# MEMS_BMI.net
KiCad netlist of a schematic drawn in EAGLE
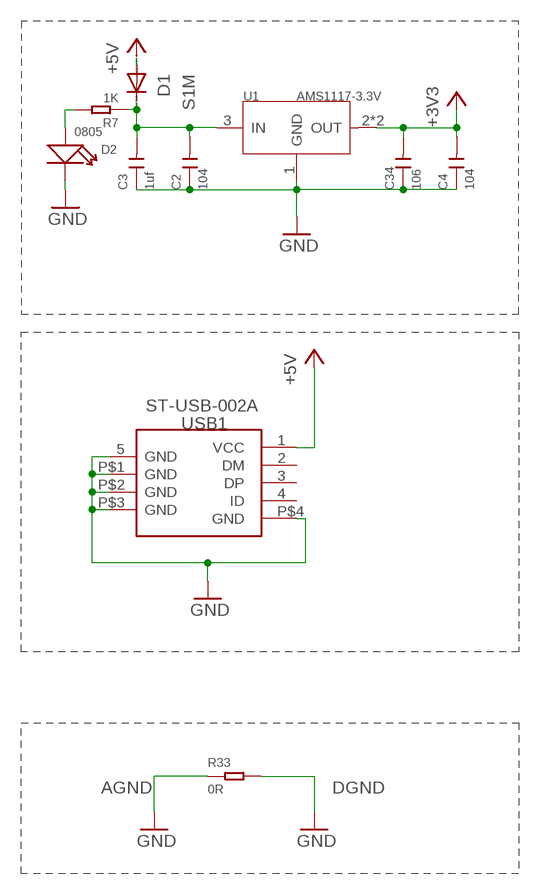
[diagram p0: schematic, sheet 1]
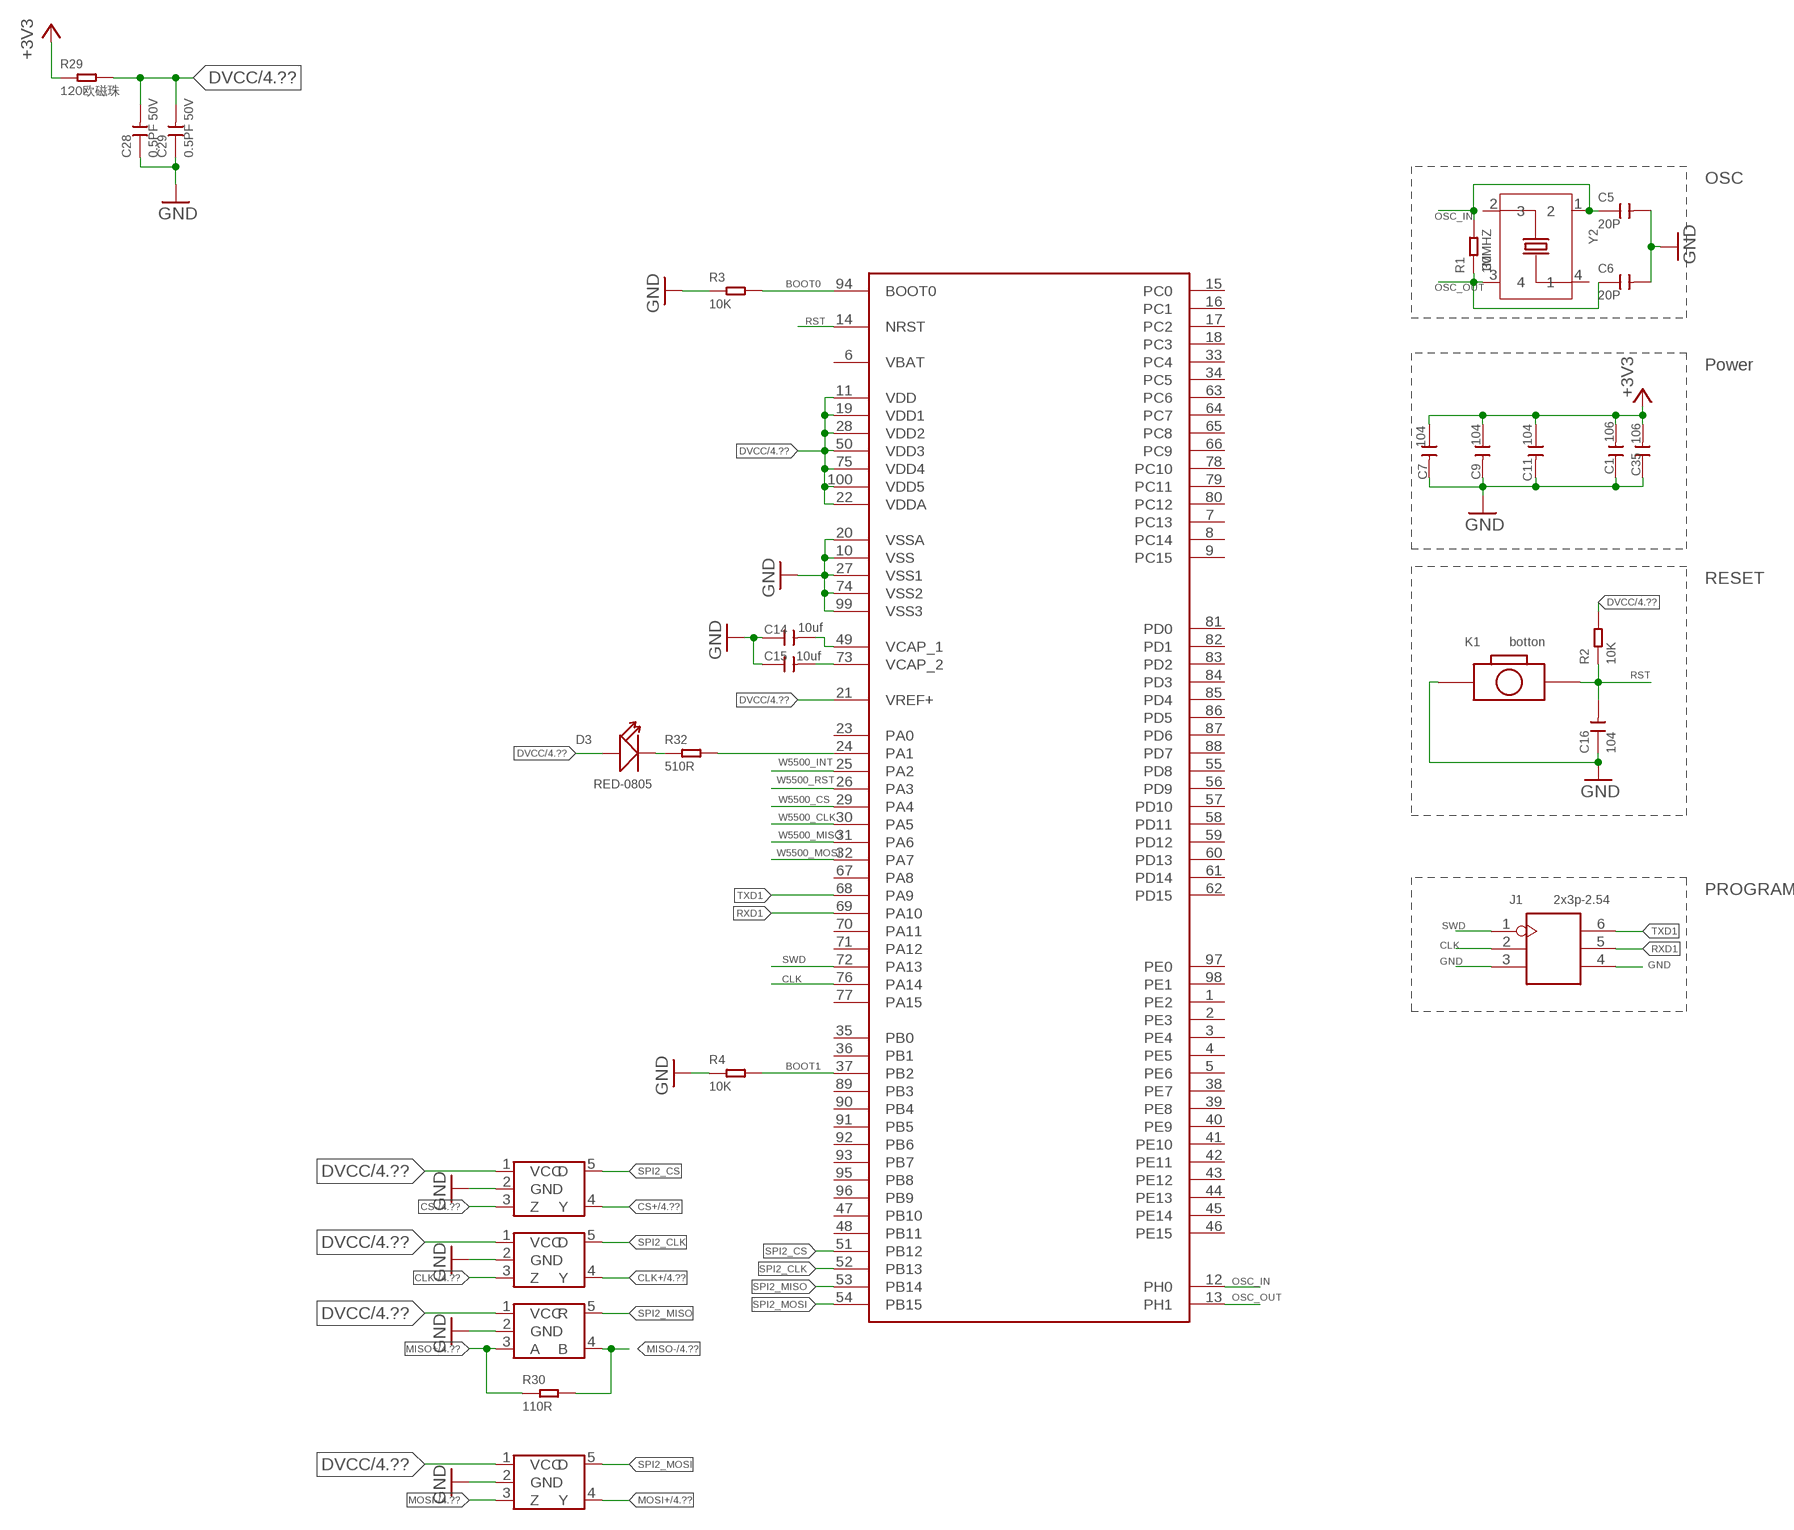
[diagram p1: schematic, sheet 2]
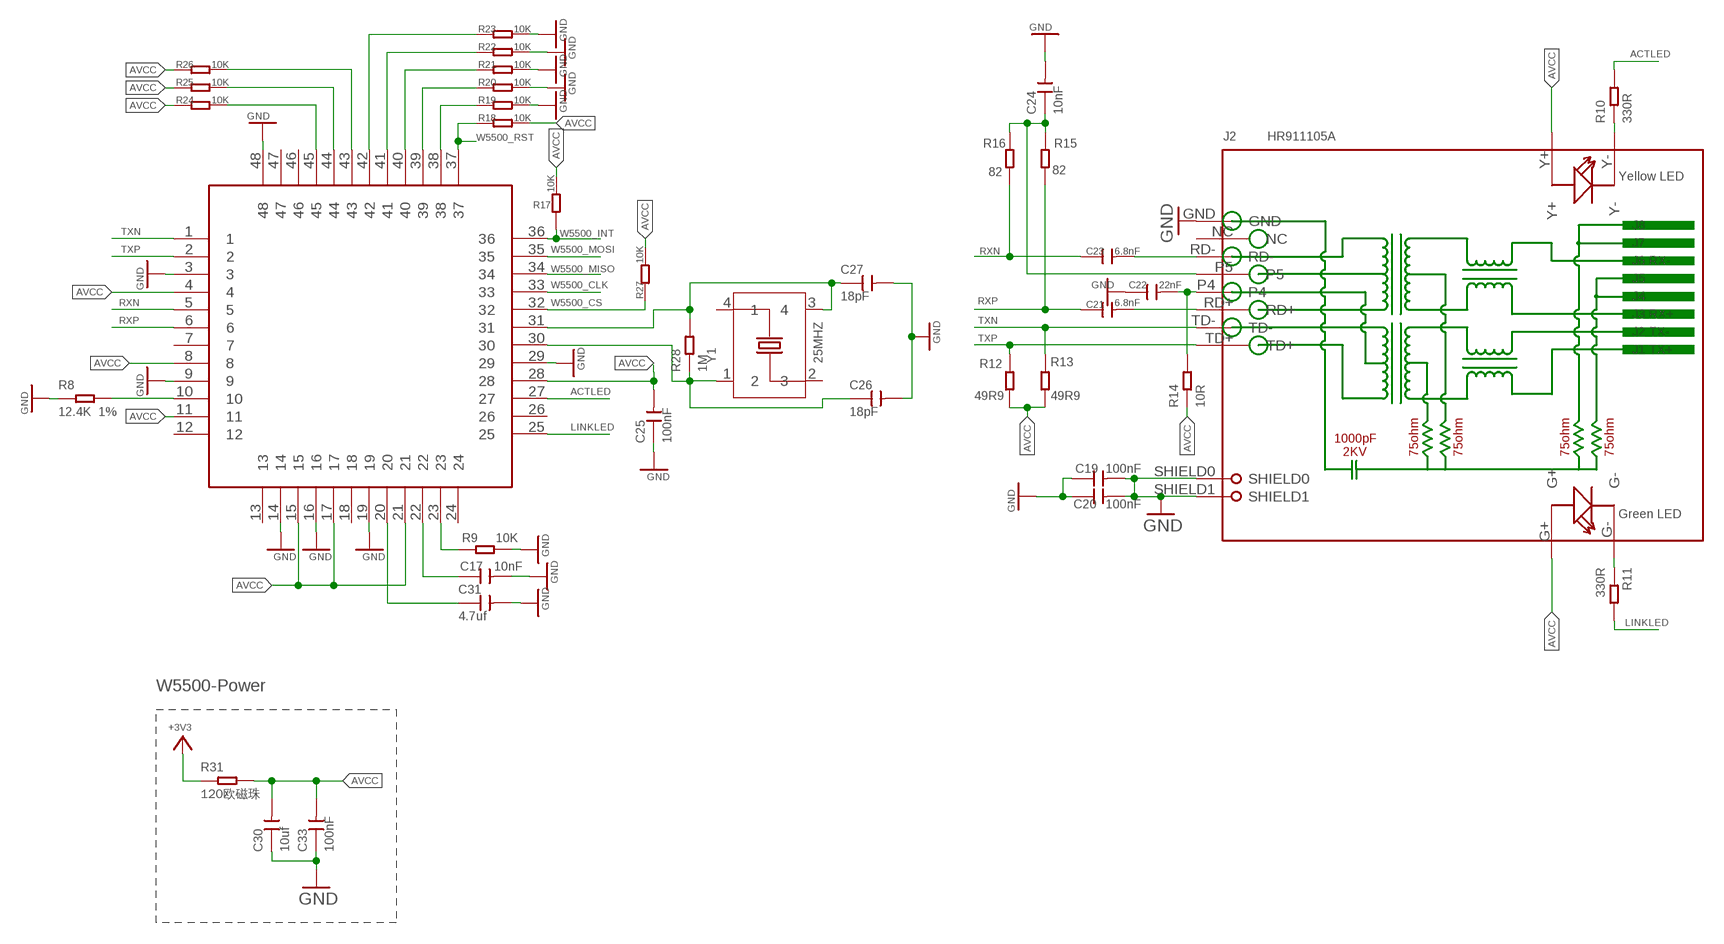
[diagram p2: schematic, sheet 3]
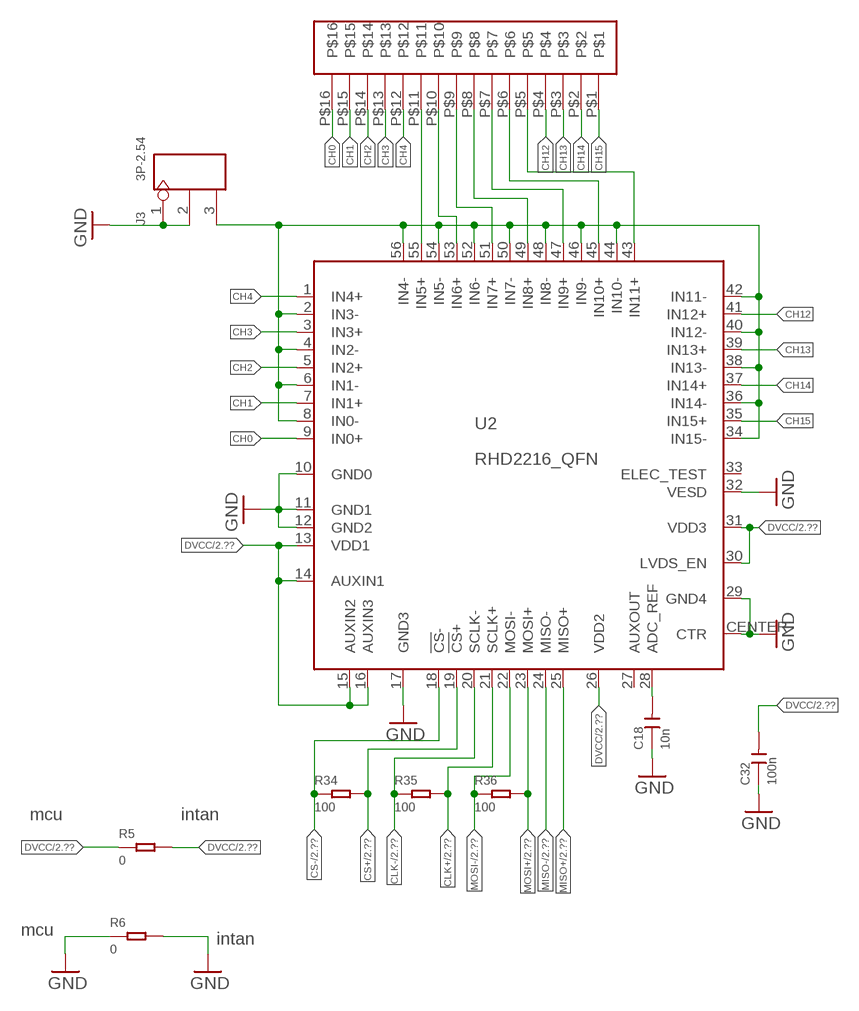
[diagram p3: schematic, sheet 4]

(export (version "E")
  (design (tool "Eeschema 10.0.6"))
  (components
    (comp (ref "C17")
      (value "10nF")
      (footprint "eagle-import:C0603")
      (libsource (lib "eagle-import") (part "CAP-(0603)"))
    )
    (comp (ref "C19")
      (value "100nF")
      (footprint "eagle-import:C0603")
      (libsource (lib "eagle-import") (part "CAP-(0603)"))
    )
    (comp (ref "C20")
      (value "100nF")
      (footprint "eagle-import:C0603")
      (libsource (lib "eagle-import") (part "CAP-(0603)"))
    )
    (comp (ref "C21")
      (value "6.8nF")
      (footprint "eagle-import:C0603")
      (libsource (lib "eagle-import") (part "CAP-(0603)"))
    )
    (comp (ref "C22")
      (value "22nF")
      (footprint "eagle-import:C0603")
      (libsource (lib "eagle-import") (part "CAP-(0603)"))
    )
    (comp (ref "C23")
      (value "6.8nF")
      (footprint "eagle-import:C0603")
      (libsource (lib "eagle-import") (part "CAP-(0603)"))
    )
    (comp (ref "C24")
      (value "10nF")
      (footprint "eagle-import:C0603")
      (libsource (lib "eagle-import") (part "CAP-(0603)"))
    )
    (comp (ref "C25")
      (value "100nF")
      (footprint "eagle-import:C0603")
      (libsource (lib "eagle-import") (part "CAP-(0603)"))
    )
    (comp (ref "C26")
      (value "18pF")
      (footprint "eagle-import:C0603")
      (libsource (lib "eagle-import") (part "CAP-(0603)"))
    )
    (comp (ref "C27")
      (value "18pF")
      (footprint "eagle-import:C0603")
      (libsource (lib "eagle-import") (part "CAP-(0603)"))
    )
    (comp (ref "C30")
      (value "10uf")
      (footprint "eagle-import:C0805")
      (fields (field (name "MPN") "CC0805KKX7R8BB105"))
      (libsource (lib "eagle-import") (part "CERAMIC-1UF-25V-10%-X7R(0805)"))
    )
    (comp (ref "C31")
      (value "4.7uf")
      (footprint "eagle-import:C0805")
      (fields (field (name "MPN") "CC0805KKX7R8BB105"))
      (libsource (lib "eagle-import") (part "CERAMIC-1UF-25V-10%-X7R(0805)"))
    )
    (comp (ref "C33")
      (value "100nF")
      (footprint "eagle-import:C0603")
      (libsource (lib "eagle-import") (part "CAP-(0603)"))
    )
    (comp (ref "J2")
      (value "HR911105A")
      (footprint "eagle-import:RJ45-12+2P-21.3X16.04X13.4MM")
      (libsource (lib "eagle-import") (part "DIP-RJ45-CONNECTOR(HR911105A)"))
    )
    (comp (ref "R8")
      (value "12.4K 1%")
      (footprint "eagle-import:R0603")
      (fields (field (name "MPN") "RC0603FR-071M1L"))
      (libsource (lib "eagle-import") (part "RES-(0603)"))
    )
    (comp (ref "R9")
      (value "10K")
      (footprint "eagle-import:R0603")
      (fields (field (name "MPN") "RC0603FR-071M1L"))
      (libsource (lib "eagle-import") (part "RES-(0603)"))
    )
    (comp (ref "R10")
      (value "330R")
      (footprint "eagle-import:R0603")
      (fields (field (name "MPN") "RC0603FR-071M1L"))
      (libsource (lib "eagle-import") (part "RES-(0603)"))
    )
    (comp (ref "R11")
      (value "330R")
      (footprint "eagle-import:R0603")
      (fields (field (name "MPN") "RC0603FR-071M1L"))
      (libsource (lib "eagle-import") (part "RES-(0603)"))
    )
    (comp (ref "R12")
      (value "49R9")
      (footprint "eagle-import:R0603")
      (fields (field (name "MPN") "RC0603FR-071M1L"))
      (libsource (lib "eagle-import") (part "RES-(0603)"))
    )
    (comp (ref "R13")
      (value "49R9")
      (footprint "eagle-import:R0603")
      (fields (field (name "MPN") "RC0603FR-071M1L"))
      (libsource (lib "eagle-import") (part "RES-(0603)"))
    )
    (comp (ref "R14")
      (value "10R")
      (footprint "eagle-import:R0603")
      (fields (field (name "MPN") "RC0603FR-071M1L"))
      (libsource (lib "eagle-import") (part "RES-(0603)"))
    )
    (comp (ref "R15")
      (value "82")
      (footprint "eagle-import:R0603")
      (fields (field (name "MPN") "RC0603FR-071M1L"))
      (libsource (lib "eagle-import") (part "RES-(0603)"))
    )
    (comp (ref "R16")
      (value "82")
      (footprint "eagle-import:R0603")
      (fields (field (name "MPN") "RC0603FR-071M1L"))
      (libsource (lib "eagle-import") (part "RES-(0603)"))
    )
    (comp (ref "R17")
      (value "10K")
      (footprint "eagle-import:R0603")
      (fields (field (name "MPN") "RC0603FR-071M1L"))
      (libsource (lib "eagle-import") (part "RES-(0603)"))
    )
    (comp (ref "R18")
      (value "10K")
      (footprint "eagle-import:R0603")
      (fields (field (name "MPN") "RC0603FR-071M1L"))
      (libsource (lib "eagle-import") (part "RES-(0603)"))
    )
    (comp (ref "R19")
      (value "10K")
      (footprint "eagle-import:R0603")
      (fields (field (name "MPN") "RC0603FR-071M1L"))
      (libsource (lib "eagle-import") (part "RES-(0603)"))
    )
    (comp (ref "R20")
      (value "10K")
      (footprint "eagle-import:R0603")
      (fields (field (name "MPN") "RC0603FR-071M1L"))
      (libsource (lib "eagle-import") (part "RES-(0603)"))
    )
    (comp (ref "R21")
      (value "10K")
      (footprint "eagle-import:R0603")
      (fields (field (name "MPN") "RC0603FR-071M1L"))
      (libsource (lib "eagle-import") (part "RES-(0603)"))
    )
    (comp (ref "R22")
      (value "10K")
      (footprint "eagle-import:R0603")
      (fields (field (name "MPN") "RC0603FR-071M1L"))
      (libsource (lib "eagle-import") (part "RES-(0603)"))
    )
    (comp (ref "R23")
      (value "10K")
      (footprint "eagle-import:R0603")
      (fields (field (name "MPN") "RC0603FR-071M1L"))
      (libsource (lib "eagle-import") (part "RES-(0603)"))
    )
    (comp (ref "R24")
      (value "10K")
      (footprint "eagle-import:R0603")
      (fields (field (name "MPN") "RC0603FR-071M1L"))
      (libsource (lib "eagle-import") (part "RES-(0603)"))
    )
    (comp (ref "R25")
      (value "10K")
      (footprint "eagle-import:R0603")
      (fields (field (name "MPN") "RC0603FR-071M1L"))
      (libsource (lib "eagle-import") (part "RES-(0603)"))
    )
    (comp (ref "R26")
      (value "10K")
      (footprint "eagle-import:R0603")
      (fields (field (name "MPN") "RC0603FR-071M1L"))
      (libsource (lib "eagle-import") (part "RES-(0603)"))
    )
    (comp (ref "R27")
      (value "10K")
      (footprint "eagle-import:R0603")
      (fields (field (name "MPN") "RC0603FR-071M1L"))
      (libsource (lib "eagle-import") (part "RES-(0603)"))
    )
    (comp (ref "R28")
      (value "1M")
      (footprint "eagle-import:R0603")
      (fields (field (name "MPN") "RC0603FR-071M1L"))
      (libsource (lib "eagle-import") (part "RES-(0603)"))
    )
    (comp (ref "R31")
      (value "120欧磁珠")
      (footprint "eagle-import:R0603")
      (fields (field (name "MPN") "RC0603FR-071M1L"))
      (libsource (lib "eagle-import") (part "RES-(0603)"))
    )
    (comp (ref "W5500-1")
      (value "W5500")
      (footprint "eagle-import:LQFP48")
      (libsource (lib "eagle-import") (part "W5500"))
    )
    (comp (ref "Y1")
      (value "25MHZ")
      (footprint "eagle-import:X4-SMD-3.2X2.5X0.7MM")
      (fields (field (name "MPN") "7M30000024"))
      (libsource (lib "eagle-import") (part "SMD-CRYSTAL-30MHZ-10PF-10PPM-60R(4P-3.2X2.5MM)"))
    )
    (comp (ref "C2")
      (value "104")
      (footprint "eagle-import:C0603")
      (libsource (lib "eagle-import") (part "CAP-(0603)"))
    )
    (comp (ref "C3")
      (value "1uf")
      (footprint "eagle-import:C0805")
      (fields (field (name "MPN") "CC0805KKX7R8BB105"))
      (libsource (lib "eagle-import") (part "CERAMIC-1UF-25V-10%-X7R(0805)"))
    )
    (comp (ref "C4")
      (value "104")
      (footprint "eagle-import:C0603")
      (libsource (lib "eagle-import") (part "CAP-(0603)"))
    )
    (comp (ref "C34")
      (value "106")
      (footprint "eagle-import:C0805")
      (fields (field (name "MPN") "CC0805KKX7R8BB105"))
      (libsource (lib "eagle-import") (part "CERAMIC-1UF-25V-10%-X7R(0805)"))
    )
    (comp (ref "D1")
      (value "S1M")
      (footprint "eagle-import:SMA")
      (libsource (lib "eagle-import") (part "S1M"))
    )
    (comp (ref "D2")
      (value "0805")
      (footprint "eagle-import:LED-0805")
      (fields (field (name "MPN") "17-215SURC/S530-A2/TR8"))
      (libsource (lib "eagle-import") (part "SMD-LED-CLEAR-RED(0805)"))
    )
    (comp (ref "R7")
      (value "1K")
      (footprint "eagle-import:R0603")
      (fields (field (name "MPN") "RC0603FR-071M1L"))
      (libsource (lib "eagle-import") (part "RES-(0603)"))
    )
    (comp (ref "R33")
      (value "0R")
      (footprint "eagle-import:R0603")
      (fields (field (name "MPN") "RC0603FR-071M1L"))
      (libsource (lib "eagle-import") (part "RES-(0603)"))
    )
    (comp (ref "U1")
      (value "AMS1117-3.3V")
      (footprint "eagle-import:SOT-223")
      (fields (field (name "MPN") "CJT1117-3.3"))
      (libsource (lib "eagle-import") (part "PMIC-CJT1117-3.3(SOT223)"))
    )
    (comp (ref "USB1")
      (value "ST-USB-002A")
      (footprint "eagle-import:MINIUSB5+4P-SMD-0.8-90D")
      (libsource (lib "eagle-import") (part "MINI-USB-RCPT-B-5PS-R/A-SMD(ST-USB-002A)"))
    )
    (comp (ref "C18")
      (value "10n")
      (footprint "eagle-import:C0603")
      (libsource (lib "eagle-import") (part "CAP-(0603)"))
    )
    (comp (ref "C32")
      (value "100n")
      (footprint "eagle-import:C0603")
      (libsource (lib "eagle-import") (part "CAP-(0603)"))
    )
    (comp (ref "J3")
      (value "3P-2.54")
      (footprint "eagle-import:H3-2.54")
      (fields (field (name "MPN") "P125-1103A0BS116A1"))
      (libsource (lib "eagle-import") (part "DIP-WHITE-MALE-HEADER-VERT(3P-2.54)"))
    )
    (comp (ref "R5")
      (value "0")
      (footprint "eagle-import:R0603")
      (fields (field (name "MPN") "RC0603FR-071M1L"))
      (libsource (lib "eagle-import") (part "RES-(0603)"))
    )
    (comp (ref "R6")
      (value "0")
      (footprint "eagle-import:R0603")
      (fields (field (name "MPN") "RC0603FR-071M1L"))
      (libsource (lib "eagle-import") (part "RES-(0603)"))
    )
    (comp (ref "R34")
      (value "100")
      (footprint "eagle-import:R0603")
      (fields (field (name "MPN") "RC0603FR-071M1L"))
      (libsource (lib "eagle-import") (part "RES-(0603)"))
    )
    (comp (ref "R35")
      (value "100")
      (footprint "eagle-import:R0603")
      (fields (field (name "MPN") "RC0603FR-071M1L"))
      (libsource (lib "eagle-import") (part "RES-(0603)"))
    )
    (comp (ref "R36")
      (value "100")
      (footprint "eagle-import:R0603")
      (fields (field (name "MPN") "RC0603FR-071M1L"))
      (libsource (lib "eagle-import") (part "RES-(0603)"))
    )
    (comp (ref "U$3")
      (value "PROBE")
      (footprint "eagle-import:PROBE-16-PIN")
      (libsource (lib "eagle-import") (part "PROBE"))
    )
    (comp (ref "U2")
      (value "RHD2216_QFN")
      (footprint "eagle-import:QFN56_8_X_8_LARGE")
      (libsource (lib "eagle-import") (part "RHD2216_QFN"))
    )
    (comp (ref "C1")
      (value "106")
      (footprint "eagle-import:C0805")
      (fields (field (name "MPN") "CC0805KKX7R8BB105"))
      (libsource (lib "eagle-import") (part "CERAMIC-1UF-25V-10%-X7R(0805)"))
    )
    (comp (ref "C5")
      (value "20P")
      (footprint "eagle-import:C0603")
      (libsource (lib "eagle-import") (part "CAP-(0603)"))
    )
    (comp (ref "C6")
      (value "20P")
      (footprint "eagle-import:C0603")
      (libsource (lib "eagle-import") (part "CAP-(0603)"))
    )
    (comp (ref "C7")
      (value "104")
      (footprint "eagle-import:C0603")
      (libsource (lib "eagle-import") (part "CAP-(0603)"))
    )
    (comp (ref "C9")
      (value "104")
      (footprint "eagle-import:C0603")
      (libsource (lib "eagle-import") (part "CAP-(0603)"))
    )
    (comp (ref "C11")
      (value "104")
      (footprint "eagle-import:C0603")
      (libsource (lib "eagle-import") (part "CAP-(0603)"))
    )
    (comp (ref "C14")
      (value "10uf")
      (footprint "eagle-import:C0805")
      (fields (field (name "MPN") "CC0805KKX7R8BB105"))
      (libsource (lib "eagle-import") (part "CERAMIC-1UF-25V-10%-X7R(0805)"))
    )
    (comp (ref "C15")
      (value "10uf")
      (footprint "eagle-import:C0805")
      (fields (field (name "MPN") "CC0805KKX7R8BB105"))
      (libsource (lib "eagle-import") (part "CERAMIC-1UF-25V-10%-X7R(0805)"))
    )
    (comp (ref "C16")
      (value "104")
      (footprint "eagle-import:C0603")
      (libsource (lib "eagle-import") (part "CAP-(0603)"))
    )
    (comp (ref "C28")
      (value "0.5PF 50V")
      (footprint "eagle-import:C0603")
      (libsource (lib "eagle-import") (part "CAP-(0603)"))
    )
    (comp (ref "C29")
      (value "0.5PF 50V")
      (footprint "eagle-import:C0603")
      (libsource (lib "eagle-import") (part "CAP-(0603)"))
    )
    (comp (ref "C35")
      (value "106")
      (footprint "eagle-import:C0805")
      (fields (field (name "MPN") "CC0805KKX7R8BB105"))
      (libsource (lib "eagle-import") (part "CERAMIC-1UF-25V-10%-X7R(0805)"))
    )
    (comp (ref "D3")
      (value "RED-0805")
      (footprint "eagle-import:LED-0805")
      (fields (field (name "MPN") "17-215SURC/S530-A2/TR8"))
      (libsource (lib "eagle-import") (part "SMD-LED-CLEAR-RED(0805)"))
    )
    (comp (ref "J1")
      (value "2x3p-2.54")
      (footprint "eagle-import:H2X3-2.54")
      (fields (field (name "MPN") "F185-1203A1BSYA1"))
      (libsource (lib "eagle-import") (part "DIP-BLACK-FEMALE-HEADER-VERT(2X3P-2.54)"))
    )
    (comp (ref "K1")
      (value "botton")
      (footprint "eagle-import:SW2-SMD-3.0X6.0_2.5")
      (fields (field (name "MPN") "B3U-1000P"))
      (libsource (lib "eagle-import") (part "SMD-BUTTON"))
    )
    (comp (ref "LVDS1-1")
      (value "SN65LVDS1")
      (footprint "eagle-import:DBV_R-PDSO-G5")
      (libsource (lib "eagle-import") (part "SN65LVDS1"))
    )
    (comp (ref "LVDS1-2")
      (value "SN65LVDS1")
      (footprint "eagle-import:DBV_R-PDSO-G5")
      (libsource (lib "eagle-import") (part "SN65LVDS1"))
    )
    (comp (ref "LVDS1-3")
      (value "SN65LVDS1")
      (footprint "eagle-import:DBV_R-PDSO-G5")
      (libsource (lib "eagle-import") (part "SN65LVDS1"))
    )
    (comp (ref "R1")
      (value "1M")
      (footprint "eagle-import:R0603")
      (fields (field (name "MPN") "RC0603FR-071M1L"))
      (libsource (lib "eagle-import") (part "RES-(0603)"))
    )
    (comp (ref "R2")
      (value "10K")
      (footprint "eagle-import:R0603")
      (fields (field (name "MPN") "RC0603FR-071M1L"))
      (libsource (lib "eagle-import") (part "RES-(0603)"))
    )
    (comp (ref "R3")
      (value "10K")
      (footprint "eagle-import:R0603")
      (fields (field (name "MPN") "RC0603FR-071M1L"))
      (libsource (lib "eagle-import") (part "RES-(0603)"))
    )
    (comp (ref "R4")
      (value "10K")
      (footprint "eagle-import:R0603")
      (fields (field (name "MPN") "RC0603FR-071M1L"))
      (libsource (lib "eagle-import") (part "RES-(0603)"))
    )
    (comp (ref "R29")
      (value "120欧磁珠")
      (footprint "eagle-import:R0603")
      (fields (field (name "MPN") "RC0603FR-071M1L"))
      (libsource (lib "eagle-import") (part "RES-(0603)"))
    )
    (comp (ref "R30")
      (value "110R")
      (footprint "eagle-import:R0603")
      (fields (field (name "MPN") "RC0603FR-071M1L"))
      (libsource (lib "eagle-import") (part "RES-(0603)"))
    )
    (comp (ref "R32")
      (value "510R")
      (footprint "eagle-import:R0603")
      (fields (field (name "MPN") "RC0603FR-071M1L"))
      (libsource (lib "eagle-import") (part "RES-(0603)"))
    )
    (comp (ref "U$1")
      (value "STM32F40XSTM32D40X")
      (footprint "eagle-import:LQFP100")
      (libsource (lib "eagle-import") (part "STM32F40XSTM32D40X"))
    )
    (comp (ref "U$2")
      (value "SN65LVDS2")
      (footprint "eagle-import:DBV_R-PDSO-G5")
      (libsource (lib "eagle-import") (part "SN65LVDS2"))
    )
    (comp (ref "Y2")
      (value "30MHZ")
      (footprint "eagle-import:X4-SMD-3.2X2.5X0.7MM")
      (fields (field (name "MPN") "7M30000024"))
      (libsource (lib "eagle-import") (part "SMD-CRYSTAL-30MHZ-10PF-10PPM-60R(4P-3.2X2.5MM)"))
    )
  )
  (nets
    (net (code "1") (name "+3V3") (class "Default")
      (node (ref "C1") (pin "2") (pinfunction "2_2") (pintype "passive"))
      (node (ref "C11") (pin "1") (pinfunction "1_1") (pintype "passive"))
      (node (ref "C34") (pin "2") (pinfunction "2_2") (pintype "passive"))
      (node (ref "C35") (pin "2") (pinfunction "2_2") (pintype "passive"))
      (node (ref "C4") (pin "2") (pinfunction "2_2") (pintype "passive"))
      (node (ref "C7") (pin "1") (pinfunction "1_1") (pintype "passive"))
      (node (ref "C9") (pin "1") (pinfunction "1_1") (pintype "passive"))
      (node (ref "R29") (pin "1") (pinfunction "1_1") (pintype "passive"))
      (node (ref "R31") (pin "1") (pinfunction "1_1") (pintype "passive"))
      (node (ref "U1") (pin "2") (pinfunction "OUT_2") (pintype "bidirectional"))
      (node (ref "U1") (pin "TER") (pinfunction "OUT_TER") (pintype "bidirectional"))
    )
    (net (code "2") (name "+5V") (class "Default")
      (node (ref "D1") (pin "A") (pinfunction "A_A") (pintype "passive"))
      (node (ref "USB1") (pin "1") (pinfunction "VCC_1") (pintype "bidirectional"))
    )
    (net (code "3") (name "ACTLED") (class "Default")
      (node (ref "R10") (pin "2") (pinfunction "2_2") (pintype "passive"))
      (node (ref "W5500-1") (pin "27") (pinfunction "27_27") (pintype "bidirectional"))
    )
    (net (code "4") (name "AVCC") (class "Default")
      (node (ref "C25") (pin "2") (pinfunction "2_2") (pintype "passive"))
      (node (ref "C30") (pin "2") (pinfunction "2_2") (pintype "passive"))
      (node (ref "C33") (pin "2") (pinfunction "2_2") (pintype "passive"))
      (node (ref "J2") (pin "G+") (pinfunction "G+_G+") (pintype "bidirectional"))
      (node (ref "J2") (pin "Y+") (pinfunction "Y+_Y+") (pintype "bidirectional"))
      (node (ref "R12") (pin "1") (pinfunction "1_1") (pintype "passive"))
      (node (ref "R13") (pin "1") (pinfunction "1_1") (pintype "passive"))
      (node (ref "R14") (pin "1") (pinfunction "1_1") (pintype "passive"))
      (node (ref "R17") (pin "2") (pinfunction "2_2") (pintype "passive"))
      (node (ref "R18") (pin "2") (pinfunction "2_2") (pintype "passive"))
      (node (ref "R24") (pin "1") (pinfunction "1_1") (pintype "passive"))
      (node (ref "R25") (pin "1") (pinfunction "1_1") (pintype "passive"))
      (node (ref "R26") (pin "1") (pinfunction "1_1") (pintype "passive"))
      (node (ref "R27") (pin "2") (pinfunction "2_2") (pintype "passive"))
      (node (ref "R31") (pin "2") (pinfunction "2_2") (pintype "passive"))
      (node (ref "W5500-1") (pin "11") (pinfunction "11_11") (pintype "bidirectional"))
      (node (ref "W5500-1") (pin "15") (pinfunction "15_15") (pintype "bidirectional"))
      (node (ref "W5500-1") (pin "17") (pinfunction "17_17") (pintype "bidirectional"))
      (node (ref "W5500-1") (pin "21") (pinfunction "21_21") (pintype "bidirectional"))
      (node (ref "W5500-1") (pin "28") (pinfunction "28_28") (pintype "bidirectional"))
      (node (ref "W5500-1") (pin "4") (pinfunction "4_4") (pintype "bidirectional"))
      (node (ref "W5500-1") (pin "8") (pinfunction "8_8") (pintype "bidirectional"))
    )
    (net (code "5") (name "BOOT0") (class "Default")
      (node (ref "R3") (pin "2") (pinfunction "2_2") (pintype "passive"))
      (node (ref "U$1") (pin "94") (pinfunction "BOOT0_94") (pintype "bidirectional"))
    )
    (net (code "6") (name "BOOT1") (class "Default")
      (node (ref "R4") (pin "2") (pinfunction "2_2") (pintype "passive"))
      (node (ref "U$1") (pin "37") (pinfunction "PB2_37") (pintype "bidirectional"))
    )
    (net (code "7") (name "CH0") (class "Default")
      (node (ref "U$3") (pin "P$16") (pinfunction "P$16_P$16") (pintype "bidirectional"))
      (node (ref "U2") (pin "9") (pinfunction "IN0+_9") (pintype "input"))
    )
    (net (code "8") (name "CH1") (class "Default")
      (node (ref "U$3") (pin "P$15") (pinfunction "P$15_P$15") (pintype "bidirectional"))
      (node (ref "U2") (pin "7") (pinfunction "IN1+_7") (pintype "input"))
    )
    (net (code "9") (name "CH2") (class "Default")
      (node (ref "U$3") (pin "P$14") (pinfunction "P$14_P$14") (pintype "bidirectional"))
      (node (ref "U2") (pin "5") (pinfunction "IN2+_5") (pintype "input"))
    )
    (net (code "10") (name "CH3") (class "Default")
      (node (ref "U$3") (pin "P$13") (pinfunction "P$13_P$13") (pintype "bidirectional"))
      (node (ref "U2") (pin "3") (pinfunction "IN3+_3") (pintype "input"))
    )
    (net (code "11") (name "CH4") (class "Default")
      (node (ref "U$3") (pin "P$12") (pinfunction "P$12_P$12") (pintype "bidirectional"))
      (node (ref "U2") (pin "1") (pinfunction "IN4+_1") (pintype "input"))
    )
    (net (code "12") (name "CH12") (class "Default")
      (node (ref "U$3") (pin "P$4") (pinfunction "P$4_P$4") (pintype "bidirectional"))
      (node (ref "U2") (pin "41") (pinfunction "IN12+_41") (pintype "input"))
    )
    (net (code "13") (name "CH13") (class "Default")
      (node (ref "U$3") (pin "P$3") (pinfunction "P$3_P$3") (pintype "bidirectional"))
      (node (ref "U2") (pin "39") (pinfunction "IN13+_39") (pintype "input"))
    )
    (net (code "14") (name "CH14") (class "Default")
      (node (ref "U$3") (pin "P$2") (pinfunction "P$2_P$2") (pintype "bidirectional"))
      (node (ref "U2") (pin "37") (pinfunction "IN14+_37") (pintype "input"))
    )
    (net (code "15") (name "CH15") (class "Default")
      (node (ref "U$3") (pin "P$1") (pinfunction "P$1_P$1") (pintype "bidirectional"))
      (node (ref "U2") (pin "35") (pinfunction "IN15+_35") (pintype "input"))
    )
    (net (code "16") (name "CLK") (class "Default")
      (node (ref "J1") (pin "2") (pinfunction "2_2") (pintype "bidirectional"))
      (node (ref "U$1") (pin "76") (pinfunction "PA14_76") (pintype "bidirectional"))
    )
    (net (code "17") (name "CLK+") (class "Default")
      (node (ref "LVDS1-2") (pin "4") (pinfunction "Y_4") (pintype "bidirectional"))
      (node (ref "R35") (pin "2") (pinfunction "2_2") (pintype "passive"))
      (node (ref "U2") (pin "21") (pinfunction "SCLK+_21") (pintype "input"))
    )
    (net (code "18") (name "CLK-") (class "Default")
      (node (ref "LVDS1-2") (pin "3") (pinfunction "Z_3") (pintype "bidirectional"))
      (node (ref "R35") (pin "1") (pinfunction "1_1") (pintype "passive"))
      (node (ref "U2") (pin "20") (pinfunction "SCLK-_20") (pintype "input"))
    )
    (net (code "19") (name "CS+") (class "Default")
      (node (ref "LVDS1-1") (pin "4") (pinfunction "Y_4") (pintype "bidirectional"))
      (node (ref "R34") (pin "2") (pinfunction "2_2") (pintype "passive"))
      (node (ref "U2") (pin "19") (pinfunction "~{CS}+_19") (pintype "input"))
    )
    (net (code "20") (name "CS-") (class "Default")
      (node (ref "LVDS1-1") (pin "3") (pinfunction "Z_3") (pintype "bidirectional"))
      (node (ref "R34") (pin "1") (pinfunction "1_1") (pintype "passive"))
      (node (ref "U2") (pin "18") (pinfunction "~{CS}-_18") (pintype "input"))
    )
    (net (code "21") (name "DVCC") (class "Default")
      (node (ref "C28") (pin "2") (pinfunction "2_2") (pintype "passive"))
      (node (ref "C29") (pin "2") (pinfunction "2_2") (pintype "passive"))
      (node (ref "C32") (pin "2") (pinfunction "2_2") (pintype "passive"))
      (node (ref "D3") (pin "+") (pinfunction "+_+") (pintype "passive"))
      (node (ref "LVDS1-1") (pin "1") (pinfunction "VCC_1") (pintype "bidirectional"))
      (node (ref "LVDS1-2") (pin "1") (pinfunction "VCC_1") (pintype "bidirectional"))
      (node (ref "LVDS1-3") (pin "1") (pinfunction "VCC_1") (pintype "bidirectional"))
      (node (ref "R2") (pin "2") (pinfunction "2_2") (pintype "passive"))
      (node (ref "R29") (pin "2") (pinfunction "2_2") (pintype "passive"))
      (node (ref "R5") (pin "1") (pinfunction "1_1") (pintype "passive"))
      (node (ref "R5") (pin "2") (pinfunction "2_2") (pintype "passive"))
      (node (ref "U$1") (pin "100") (pinfunction "VDD5_100") (pintype "bidirectional"))
      (node (ref "U$1") (pin "11") (pinfunction "VDD_11") (pintype "bidirectional"))
      (node (ref "U$1") (pin "19") (pinfunction "VDD1_19") (pintype "bidirectional"))
      (node (ref "U$1") (pin "21") (pinfunction "VREF+_21") (pintype "bidirectional"))
      (node (ref "U$1") (pin "22") (pinfunction "VDDA_22") (pintype "bidirectional"))
      (node (ref "U$1") (pin "28") (pinfunction "VDD2_28") (pintype "bidirectional"))
      (node (ref "U$1") (pin "50") (pinfunction "VDD3_50") (pintype "bidirectional"))
      (node (ref "U$1") (pin "75") (pinfunction "VDD4_75") (pintype "bidirectional"))
      (node (ref "U$2") (pin "1") (pinfunction "VCC_1") (pintype "bidirectional"))
      (node (ref "U2") (pin "13") (pinfunction "VDD1_13") (pintype "power_in"))
      (node (ref "U2") (pin "14") (pinfunction "AUXIN1_14") (pintype "input"))
      (node (ref "U2") (pin "15") (pinfunction "AUXIN2_15") (pintype "input"))
      (node (ref "U2") (pin "16") (pinfunction "AUXIN3_16") (pintype "input"))
      (node (ref "U2") (pin "26") (pinfunction "VDD2_26") (pintype "power_in"))
      (node (ref "U2") (pin "30") (pinfunction "LVDS_EN_30") (pintype "input"))
      (node (ref "U2") (pin "31") (pinfunction "VDD3_31") (pintype "power_in"))
    )
    (net (code "22") (name "GND") (class "Default")
      (node (ref "C1") (pin "1") (pinfunction "1_1") (pintype "passive"))
      (node (ref "C11") (pin "2") (pinfunction "2_2") (pintype "passive"))
      (node (ref "C14") (pin "1") (pinfunction "1_1") (pintype "passive"))
      (node (ref "C15") (pin "1") (pinfunction "1_1") (pintype "passive"))
      (node (ref "C16") (pin "1") (pinfunction "1_1") (pintype "passive"))
      (node (ref "C17") (pin "2") (pinfunction "2_2") (pintype "passive"))
      (node (ref "C18") (pin "1") (pinfunction "1_1") (pintype "passive"))
      (node (ref "C19") (pin "1") (pinfunction "1_1") (pintype "passive"))
      (node (ref "C19") (pin "2") (pinfunction "2_2") (pintype "passive"))
      (node (ref "C2") (pin "1") (pinfunction "1_1") (pintype "passive"))
      (node (ref "C20") (pin "1") (pinfunction "1_1") (pintype "passive"))
      (node (ref "C20") (pin "2") (pinfunction "2_2") (pintype "passive"))
      (node (ref "C22") (pin "1") (pinfunction "1_1") (pintype "passive"))
      (node (ref "C24") (pin "2") (pinfunction "2_2") (pintype "passive"))
      (node (ref "C25") (pin "1") (pinfunction "1_1") (pintype "passive"))
      (node (ref "C26") (pin "2") (pinfunction "2_2") (pintype "passive"))
      (node (ref "C27") (pin "2") (pinfunction "2_2") (pintype "passive"))
      (node (ref "C28") (pin "1") (pinfunction "1_1") (pintype "passive"))
      (node (ref "C29") (pin "1") (pinfunction "1_1") (pintype "passive"))
      (node (ref "C3") (pin "1") (pinfunction "1_1") (pintype "passive"))
      (node (ref "C30") (pin "1") (pinfunction "1_1") (pintype "passive"))
      (node (ref "C31") (pin "2") (pinfunction "2_2") (pintype "passive"))
      (node (ref "C32") (pin "1") (pinfunction "1_1") (pintype "passive"))
      (node (ref "C33") (pin "1") (pinfunction "1_1") (pintype "passive"))
      (node (ref "C34") (pin "1") (pinfunction "1_1") (pintype "passive"))
      (node (ref "C35") (pin "1") (pinfunction "1_1") (pintype "passive"))
      (node (ref "C4") (pin "1") (pinfunction "1_1") (pintype "passive"))
      (node (ref "C5") (pin "2") (pinfunction "2_2") (pintype "passive"))
      (node (ref "C6") (pin "2") (pinfunction "2_2") (pintype "passive"))
      (node (ref "C7") (pin "2") (pinfunction "2_2") (pintype "passive"))
      (node (ref "C9") (pin "2") (pinfunction "2_2") (pintype "passive"))
      (node (ref "D2") (pin "-") (pinfunction "-_-") (pintype "passive"))
      (node (ref "J1") (pin "3") (pinfunction "3_3") (pintype "bidirectional"))
      (node (ref "J1") (pin "4") (pinfunction "4_4") (pintype "bidirectional"))
      (node (ref "J2") (pin "GND") (pinfunction "GND_GND") (pintype "bidirectional"))
      (node (ref "J2") (pin "SHIELD0") (pinfunction "SHIELD0_SHIELD0") (pintype "bidirectional"))
      (node (ref "J2") (pin "SHIELD1") (pinfunction "SHIELD1_SHIELD1") (pintype "bidirectional"))
      (node (ref "J3") (pin "1") (pinfunction "P$1_1") (pintype "bidirectional"))
      (node (ref "J3") (pin "2") (pinfunction "P$2_2") (pintype "bidirectional"))
      (node (ref "K1") (pin "1") (pinfunction "1_1") (pintype "bidirectional"))
      (node (ref "LVDS1-1") (pin "2") (pinfunction "GND_2") (pintype "bidirectional"))
      (node (ref "LVDS1-2") (pin "2") (pinfunction "GND_2") (pintype "bidirectional"))
      (node (ref "LVDS1-3") (pin "2") (pinfunction "GND_2") (pintype "bidirectional"))
      (node (ref "R19") (pin "2") (pinfunction "2_2") (pintype "passive"))
      (node (ref "R20") (pin "2") (pinfunction "2_2") (pintype "passive"))
      (node (ref "R21") (pin "2") (pinfunction "2_2") (pintype "passive"))
      (node (ref "R22") (pin "2") (pinfunction "2_2") (pintype "passive"))
      (node (ref "R23") (pin "2") (pinfunction "2_2") (pintype "passive"))
      (node (ref "R3") (pin "1") (pinfunction "1_1") (pintype "passive"))
      (node (ref "R33") (pin "1") (pinfunction "1_1") (pintype "passive"))
      (node (ref "R33") (pin "2") (pinfunction "2_2") (pintype "passive"))
      (node (ref "R4") (pin "1") (pinfunction "1_1") (pintype "passive"))
      (node (ref "R6") (pin "1") (pinfunction "1_1") (pintype "passive"))
      (node (ref "R6") (pin "2") (pinfunction "2_2") (pintype "passive"))
      (node (ref "R8") (pin "1") (pinfunction "1_1") (pintype "passive"))
      (node (ref "R9") (pin "2") (pinfunction "2_2") (pintype "passive"))
      (node (ref "U$1") (pin "10") (pinfunction "VSS_10") (pintype "bidirectional"))
      (node (ref "U$1") (pin "20") (pinfunction "VSSA_20") (pintype "bidirectional"))
      (node (ref "U$1") (pin "27") (pinfunction "VSS1_27") (pintype "bidirectional"))
      (node (ref "U$1") (pin "74") (pinfunction "VSS2_74") (pintype "bidirectional"))
      (node (ref "U$1") (pin "99") (pinfunction "VSS3_99") (pintype "bidirectional"))
      (node (ref "U$2") (pin "2") (pinfunction "GND_2") (pintype "bidirectional"))
      (node (ref "U1") (pin "1") (pinfunction "GND_1") (pintype "bidirectional"))
      (node (ref "U2") (pin "10") (pinfunction "GND0_10") (pintype "input"))
      (node (ref "U2") (pin "11") (pinfunction "GND1_11") (pintype "power_in"))
      (node (ref "U2") (pin "12") (pinfunction "GND2_12") (pintype "power_in"))
      (node (ref "U2") (pin "17") (pinfunction "GND3_17") (pintype "power_in"))
      (node (ref "U2") (pin "29") (pinfunction "GND4_29") (pintype "power_in"))
      (node (ref "U2") (pin "32") (pinfunction "VESD_32") (pintype "power_in"))
      (node (ref "U2") (pin "CENTER") (pinfunction "CTR_CENTER") (pintype "power_in"))
      (node (ref "USB1") (pin "5") (pinfunction "GND_5") (pintype "bidirectional"))
      (node (ref "USB1") (pin "P$1") (pinfunction "GND_P$1") (pintype "bidirectional"))
      (node (ref "USB1") (pin "P$2") (pinfunction "GND_P$2") (pintype "bidirectional"))
      (node (ref "USB1") (pin "P$3") (pinfunction "GND_P$3") (pintype "bidirectional"))
      (node (ref "USB1") (pin "P$4") (pinfunction "GND_P$4") (pintype "bidirectional"))
      (node (ref "W5500-1") (pin "14") (pinfunction "14_14") (pintype "bidirectional"))
      (node (ref "W5500-1") (pin "16") (pinfunction "16_16") (pintype "bidirectional"))
      (node (ref "W5500-1") (pin "19") (pinfunction "19_19") (pintype "bidirectional"))
      (node (ref "W5500-1") (pin "29") (pinfunction "29_29") (pintype "bidirectional"))
      (node (ref "W5500-1") (pin "3") (pinfunction "3_3") (pintype "bidirectional"))
      (node (ref "W5500-1") (pin "48") (pinfunction "48_48") (pintype "bidirectional"))
      (node (ref "W5500-1") (pin "9") (pinfunction "9_9") (pintype "bidirectional"))
    )
    (net (code "23") (name "LINKLED") (class "Default")
      (node (ref "R11") (pin "2") (pinfunction "2_2") (pintype "passive"))
      (node (ref "W5500-1") (pin "25") (pinfunction "25_25") (pintype "bidirectional"))
    )
    (net (code "24") (name "MISO+") (class "Default")
      (node (ref "R30") (pin "1") (pinfunction "1_1") (pintype "passive"))
      (node (ref "U$2") (pin "3") (pinfunction "A_3") (pintype "bidirectional"))
      (node (ref "U2") (pin "25") (pinfunction "MISO+_25") (pintype "output"))
    )
    (net (code "25") (name "MISO-") (class "Default")
      (node (ref "R30") (pin "2") (pinfunction "2_2") (pintype "passive"))
      (node (ref "U$2") (pin "4") (pinfunction "B_4") (pintype "bidirectional"))
      (node (ref "U2") (pin "24") (pinfunction "MISO-_24") (pintype "output"))
    )
    (net (code "26") (name "MOSI+") (class "Default")
      (node (ref "LVDS1-3") (pin "4") (pinfunction "Y_4") (pintype "bidirectional"))
      (node (ref "R36") (pin "2") (pinfunction "2_2") (pintype "passive"))
      (node (ref "U2") (pin "23") (pinfunction "MOSI+_23") (pintype "input"))
    )
    (net (code "27") (name "MOSI-") (class "Default")
      (node (ref "LVDS1-3") (pin "3") (pinfunction "Z_3") (pintype "bidirectional"))
      (node (ref "R36") (pin "1") (pinfunction "1_1") (pintype "passive"))
      (node (ref "U2") (pin "22") (pinfunction "MOSI-_22") (pintype "input"))
    )
    (net (code "28") (name "Net-(C17-Pad1)") (class "Default")
      (node (ref "C17") (pin "1") (pinfunction "1_1") (pintype "passive"))
      (node (ref "W5500-1") (pin "22") (pinfunction "22_22") (pintype "bidirectional"))
    )
    (net (code "29") (name "Net-(C21-Pad2)") (class "Default")
      (node (ref "C21") (pin "2") (pinfunction "2_2") (pintype "passive"))
      (node (ref "J2") (pin "RD+") (pinfunction "RD+_RD+") (pintype "bidirectional"))
    )
    (net (code "30") (name "Net-(C22-Pad2)") (class "Default")
      (node (ref "C22") (pin "2") (pinfunction "2_2") (pintype "passive"))
      (node (ref "J2") (pin "P4") (pinfunction "P4_P4") (pintype "bidirectional"))
      (node (ref "R14") (pin "2") (pinfunction "2_2") (pintype "passive"))
    )
    (net (code "31") (name "Net-(C23-Pad2)") (class "Default")
      (node (ref "C23") (pin "2") (pinfunction "2_2") (pintype "passive"))
      (node (ref "J2") (pin "RD-") (pinfunction "RD-_RD-") (pintype "bidirectional"))
    )
    (net (code "32") (name "Net-(C24-Pad1)") (class "Default")
      (node (ref "C24") (pin "1") (pinfunction "1_1") (pintype "passive"))
      (node (ref "J2") (pin "P5") (pinfunction "P5_P5") (pintype "bidirectional"))
      (node (ref "R15") (pin "2") (pinfunction "2_2") (pintype "passive"))
      (node (ref "R16") (pin "2") (pinfunction "2_2") (pintype "passive"))
    )
    (net (code "33") (name "Net-(C31-Pad1)") (class "Default")
      (node (ref "C31") (pin "1") (pinfunction "1_1") (pintype "passive"))
      (node (ref "W5500-1") (pin "20") (pinfunction "20_20") (pintype "bidirectional"))
    )
    (net (code "34") (name "Net-(D2-Pad+)") (class "Default")
      (node (ref "D2") (pin "+") (pinfunction "+_+") (pintype "passive"))
      (node (ref "R7") (pin "2") (pinfunction "2_2") (pintype "passive"))
    )
    (net (code "35") (name "Net-(D3-Pad-)") (class "Default")
      (node (ref "D3") (pin "-") (pinfunction "-_-") (pintype "passive"))
      (node (ref "R32") (pin "1") (pinfunction "1_1") (pintype "passive"))
    )
    (net (code "36") (name "Net-(J2-PadG-)") (class "Default")
      (node (ref "J2") (pin "G-") (pinfunction "G-_G-") (pintype "bidirectional"))
      (node (ref "R11") (pin "1") (pinfunction "1_1") (pintype "passive"))
    )
    (net (code "37") (name "Net-(J2-PadY-)") (class "Default")
      (node (ref "J2") (pin "Y-") (pinfunction "Y-_Y-") (pintype "bidirectional"))
      (node (ref "R10") (pin "1") (pinfunction "1_1") (pintype "passive"))
    )
    (net (code "38") (name "Net-(J3-P$3)") (class "Default")
      (node (ref "J3") (pin "3") (pinfunction "P$3_3") (pintype "bidirectional"))
      (node (ref "U2") (pin "2") (pinfunction "IN3-_2") (pintype "input"))
      (node (ref "U2") (pin "34") (pinfunction "IN15-_34") (pintype "input"))
      (node (ref "U2") (pin "36") (pinfunction "IN14-_36") (pintype "input"))
      (node (ref "U2") (pin "38") (pinfunction "IN13-_38") (pintype "input"))
      (node (ref "U2") (pin "4") (pinfunction "IN2-_4") (pintype "input"))
      (node (ref "U2") (pin "40") (pinfunction "IN12-_40") (pintype "input"))
      (node (ref "U2") (pin "42") (pinfunction "IN11-_42") (pintype "input"))
      (node (ref "U2") (pin "44") (pinfunction "IN10-_44") (pintype "input"))
      (node (ref "U2") (pin "46") (pinfunction "IN9-_46") (pintype "input"))
      (node (ref "U2") (pin "48") (pinfunction "IN8-_48") (pintype "input"))
      (node (ref "U2") (pin "50") (pinfunction "IN7-_50") (pintype "input"))
      (node (ref "U2") (pin "52") (pinfunction "IN6-_52") (pintype "input"))
      (node (ref "U2") (pin "54") (pinfunction "IN5-_54") (pintype "input"))
      (node (ref "U2") (pin "56") (pinfunction "IN4-_56") (pintype "input"))
      (node (ref "U2") (pin "6") (pinfunction "IN1-_6") (pintype "input"))
      (node (ref "U2") (pin "8") (pinfunction "IN0-_8") (pintype "input"))
    )
    (net (code "39") (name "Net-(R8-Pad2)") (class "Default")
      (node (ref "R8") (pin "2") (pinfunction "2_2") (pintype "passive"))
      (node (ref "W5500-1") (pin "10") (pinfunction "10_10") (pintype "bidirectional"))
    )
    (net (code "40") (name "Net-(R9-Pad1)") (class "Default")
      (node (ref "R9") (pin "1") (pinfunction "1_1") (pintype "passive"))
      (node (ref "W5500-1") (pin "23") (pinfunction "23_23") (pintype "bidirectional"))
    )
    (net (code "41") (name "Net-(R19-Pad1)") (class "Default")
      (node (ref "R19") (pin "1") (pinfunction "1_1") (pintype "passive"))
      (node (ref "W5500-1") (pin "38") (pinfunction "38_38") (pintype "bidirectional"))
    )
    (net (code "42") (name "Net-(R20-Pad1)") (class "Default")
      (node (ref "R20") (pin "1") (pinfunction "1_1") (pintype "passive"))
      (node (ref "W5500-1") (pin "39") (pinfunction "39_39") (pintype "bidirectional"))
    )
    (net (code "43") (name "Net-(R21-Pad1)") (class "Default")
      (node (ref "R21") (pin "1") (pinfunction "1_1") (pintype "passive"))
      (node (ref "W5500-1") (pin "40") (pinfunction "40_40") (pintype "bidirectional"))
    )
    (net (code "44") (name "Net-(R22-Pad1)") (class "Default")
      (node (ref "R22") (pin "1") (pinfunction "1_1") (pintype "passive"))
      (node (ref "W5500-1") (pin "41") (pinfunction "41_41") (pintype "bidirectional"))
    )
    (net (code "45") (name "Net-(R23-Pad1)") (class "Default")
      (node (ref "R23") (pin "1") (pinfunction "1_1") (pintype "passive"))
      (node (ref "W5500-1") (pin "42") (pinfunction "42_42") (pintype "bidirectional"))
    )
    (net (code "46") (name "Net-(R24-Pad2)") (class "Default")
      (node (ref "R24") (pin "2") (pinfunction "2_2") (pintype "passive"))
      (node (ref "W5500-1") (pin "45") (pinfunction "45_45") (pintype "bidirectional"))
    )
    (net (code "47") (name "Net-(R25-Pad2)") (class "Default")
      (node (ref "R25") (pin "2") (pinfunction "2_2") (pintype "passive"))
      (node (ref "W5500-1") (pin "44") (pinfunction "44_44") (pintype "bidirectional"))
    )
    (net (code "48") (name "Net-(R26-Pad2)") (class "Default")
      (node (ref "R26") (pin "2") (pinfunction "2_2") (pintype "passive"))
      (node (ref "W5500-1") (pin "43") (pinfunction "43_43") (pintype "bidirectional"))
    )
    (net (code "49") (name "Net-(U$1-PA1)") (class "Default")
      (node (ref "R32") (pin "2") (pinfunction "2_2") (pintype "passive"))
      (node (ref "U$1") (pin "24") (pinfunction "PA1_24") (pintype "bidirectional"))
    )
    (net (code "50") (name "Net-(U$1-VCAP_1)") (class "Default")
      (node (ref "C14") (pin "2") (pinfunction "2_2") (pintype "passive"))
      (node (ref "U$1") (pin "49") (pinfunction "VCAP_1_49") (pintype "bidirectional"))
    )
    (net (code "51") (name "Net-(U$1-VCAP_2)") (class "Default")
      (node (ref "C15") (pin "2") (pinfunction "2_2") (pintype "passive"))
      (node (ref "U$1") (pin "73") (pinfunction "VCAP_2_73") (pintype "bidirectional"))
    )
    (net (code "52") (name "Net-(U1-IN)") (class "Default")
      (node (ref "C2") (pin "2") (pinfunction "2_2") (pintype "passive"))
      (node (ref "C3") (pin "2") (pinfunction "2_2") (pintype "passive"))
      (node (ref "D1") (pin "C") (pinfunction "C_C") (pintype "passive"))
      (node (ref "R7") (pin "1") (pinfunction "1_1") (pintype "passive"))
      (node (ref "U1") (pin "3") (pinfunction "IN_3") (pintype "bidirectional"))
    )
    (net (code "53") (name "Net-(U2-ADC_REF)") (class "Default")
      (node (ref "C18") (pin "2") (pinfunction "2_2") (pintype "passive"))
      (node (ref "U2") (pin "28") (pinfunction "ADC_REF_28") (pintype "passive"))
    )
    (net (code "54") (name "Net-(U2-IN5+)") (class "Default")
      (node (ref "U$3") (pin "P$11") (pinfunction "P$11_P$11") (pintype "bidirectional"))
      (node (ref "U2") (pin "55") (pinfunction "IN5+_55") (pintype "input"))
    )
    (net (code "55") (name "Net-(U2-IN6+)") (class "Default")
      (node (ref "U$3") (pin "P$10") (pinfunction "P$10_P$10") (pintype "bidirectional"))
      (node (ref "U2") (pin "53") (pinfunction "IN6+_53") (pintype "input"))
    )
    (net (code "56") (name "Net-(U2-IN7+)") (class "Default")
      (node (ref "U$3") (pin "P$9") (pinfunction "P$9_P$9") (pintype "bidirectional"))
      (node (ref "U2") (pin "51") (pinfunction "IN7+_51") (pintype "input"))
    )
    (net (code "57") (name "Net-(U2-IN8+)") (class "Default")
      (node (ref "U$3") (pin "P$8") (pinfunction "P$8_P$8") (pintype "bidirectional"))
      (node (ref "U2") (pin "49") (pinfunction "IN8+_49") (pintype "input"))
    )
    (net (code "58") (name "Net-(U2-IN9+)") (class "Default")
      (node (ref "U$3") (pin "P$7") (pinfunction "P$7_P$7") (pintype "bidirectional"))
      (node (ref "U2") (pin "47") (pinfunction "IN9+_47") (pintype "input"))
    )
    (net (code "59") (name "Net-(U2-IN10+)") (class "Default")
      (node (ref "U$3") (pin "P$6") (pinfunction "P$6_P$6") (pintype "bidirectional"))
      (node (ref "U2") (pin "45") (pinfunction "IN10+_45") (pintype "input"))
    )
    (net (code "60") (name "Net-(U2-IN11+)") (class "Default")
      (node (ref "U$3") (pin "P$5") (pinfunction "P$5_P$5") (pintype "bidirectional"))
      (node (ref "U2") (pin "43") (pinfunction "IN11+_43") (pintype "input"))
    )
    (net (code "61") (name "Net-(Y1-2)") (class "Default")
      (node (ref "C26") (pin "1") (pinfunction "1_1") (pintype "passive"))
      (node (ref "R28") (pin "1") (pinfunction "1_1") (pintype "passive"))
      (node (ref "W5500-1") (pin "30") (pinfunction "30_30") (pintype "bidirectional"))
      (node (ref "Y1") (pin "1") (pinfunction "2_1") (pintype "bidirectional"))
    )
    (net (code "62") (name "Net-(Y1-4)") (class "Default")
      (node (ref "C27") (pin "1") (pinfunction "1_1") (pintype "passive"))
      (node (ref "R28") (pin "2") (pinfunction "2_2") (pintype "passive"))
      (node (ref "W5500-1") (pin "31") (pinfunction "31_31") (pintype "bidirectional"))
      (node (ref "Y1") (pin "3") (pinfunction "4_3") (pintype "bidirectional"))
    )
    (net (code "63") (name "OSC_IN") (class "Default")
      (node (ref "C5") (pin "1") (pinfunction "1_1") (pintype "passive"))
      (node (ref "R1") (pin "2") (pinfunction "2_2") (pintype "passive"))
      (node (ref "U$1") (pin "12") (pinfunction "PH0_12") (pintype "bidirectional"))
      (node (ref "Y2") (pin "1") (pinfunction "2_1") (pintype "bidirectional"))
    )
    (net (code "64") (name "OSC_OUT") (class "Default")
      (node (ref "C6") (pin "1") (pinfunction "1_1") (pintype "passive"))
      (node (ref "R1") (pin "1") (pinfunction "1_1") (pintype "passive"))
      (node (ref "U$1") (pin "13") (pinfunction "PH1_13") (pintype "bidirectional"))
      (node (ref "Y2") (pin "3") (pinfunction "4_3") (pintype "bidirectional"))
    )
    (net (code "65") (name "RST") (class "Default")
      (node (ref "C16") (pin "2") (pinfunction "2_2") (pintype "passive"))
      (node (ref "K1") (pin "2") (pinfunction "2_2") (pintype "bidirectional"))
      (node (ref "R2") (pin "1") (pinfunction "1_1") (pintype "passive"))
      (node (ref "U$1") (pin "14") (pinfunction "NRST_14") (pintype "bidirectional"))
    )
    (net (code "66") (name "RXD1") (class "Default")
      (node (ref "J1") (pin "5") (pinfunction "5_5") (pintype "bidirectional"))
      (node (ref "U$1") (pin "69") (pinfunction "PA10_69") (pintype "bidirectional"))
    )
    (net (code "67") (name "RXN") (class "Default")
      (node (ref "C23") (pin "1") (pinfunction "1_1") (pintype "passive"))
      (node (ref "R16") (pin "1") (pinfunction "1_1") (pintype "passive"))
      (node (ref "W5500-1") (pin "5") (pinfunction "5_5") (pintype "bidirectional"))
    )
    (net (code "68") (name "RXP") (class "Default")
      (node (ref "C21") (pin "1") (pinfunction "1_1") (pintype "passive"))
      (node (ref "R15") (pin "1") (pinfunction "1_1") (pintype "passive"))
      (node (ref "W5500-1") (pin "6") (pinfunction "6_6") (pintype "bidirectional"))
    )
    (net (code "69") (name "SPI2_CLK") (class "Default")
      (node (ref "LVDS1-2") (pin "5") (pinfunction "D_5") (pintype "bidirectional"))
      (node (ref "U$1") (pin "52") (pinfunction "PB13_52") (pintype "bidirectional"))
    )
    (net (code "70") (name "SPI2_CS") (class "Default")
      (node (ref "LVDS1-1") (pin "5") (pinfunction "D_5") (pintype "bidirectional"))
      (node (ref "U$1") (pin "51") (pinfunction "PB12_51") (pintype "bidirectional"))
    )
    (net (code "71") (name "SPI2_MISO") (class "Default")
      (node (ref "U$1") (pin "53") (pinfunction "PB14_53") (pintype "bidirectional"))
      (node (ref "U$2") (pin "5") (pinfunction "R_5") (pintype "bidirectional"))
    )
    (net (code "72") (name "SPI2_MOSI") (class "Default")
      (node (ref "LVDS1-3") (pin "5") (pinfunction "D_5") (pintype "bidirectional"))
      (node (ref "U$1") (pin "54") (pinfunction "PB15_54") (pintype "bidirectional"))
    )
    (net (code "73") (name "SWD") (class "Default")
      (node (ref "J1") (pin "1") (pinfunction "1_1") (pintype "bidirectional"))
      (node (ref "U$1") (pin "72") (pinfunction "PA13_72") (pintype "bidirectional"))
    )
    (net (code "74") (name "TXD1") (class "Default")
      (node (ref "J1") (pin "6") (pinfunction "6_6") (pintype "bidirectional"))
      (node (ref "U$1") (pin "68") (pinfunction "PA9_68") (pintype "bidirectional"))
    )
    (net (code "75") (name "TXN") (class "Default")
      (node (ref "J2") (pin "TD-") (pinfunction "TD-_TD-") (pintype "bidirectional"))
      (node (ref "R13") (pin "2") (pinfunction "2_2") (pintype "passive"))
      (node (ref "W5500-1") (pin "1") (pinfunction "1_1") (pintype "bidirectional"))
    )
    (net (code "76") (name "TXP") (class "Default")
      (node (ref "J2") (pin "TD+") (pinfunction "TD+_TD+") (pintype "bidirectional"))
      (node (ref "R12") (pin "2") (pinfunction "2_2") (pintype "passive"))
      (node (ref "W5500-1") (pin "2") (pinfunction "2_2") (pintype "bidirectional"))
    )
    (net (code "77") (name "W5500_CLK") (class "Default")
      (node (ref "U$1") (pin "30") (pinfunction "PA5_30") (pintype "bidirectional"))
      (node (ref "W5500-1") (pin "33") (pinfunction "33_33") (pintype "bidirectional"))
    )
    (net (code "78") (name "W5500_CS") (class "Default")
      (node (ref "R27") (pin "1") (pinfunction "1_1") (pintype "passive"))
      (node (ref "U$1") (pin "29") (pinfunction "PA4_29") (pintype "bidirectional"))
      (node (ref "W5500-1") (pin "32") (pinfunction "32_32") (pintype "bidirectional"))
    )
    (net (code "79") (name "W5500_INT") (class "Default")
      (node (ref "R17") (pin "1") (pinfunction "1_1") (pintype "passive"))
      (node (ref "U$1") (pin "25") (pinfunction "PA2_25") (pintype "bidirectional"))
      (node (ref "W5500-1") (pin "36") (pinfunction "36_36") (pintype "bidirectional"))
    )
    (net (code "80") (name "W5500_MISO") (class "Default")
      (node (ref "U$1") (pin "31") (pinfunction "PA6_31") (pintype "bidirectional"))
      (node (ref "W5500-1") (pin "34") (pinfunction "34_34") (pintype "bidirectional"))
    )
    (net (code "81") (name "W5500_MOSI") (class "Default")
      (node (ref "U$1") (pin "32") (pinfunction "PA7_32") (pintype "bidirectional"))
      (node (ref "W5500-1") (pin "35") (pinfunction "35_35") (pintype "bidirectional"))
    )
    (net (code "82") (name "W5500_RST") (class "Default")
      (node (ref "R18") (pin "1") (pinfunction "1_1") (pintype "passive"))
      (node (ref "U$1") (pin "26") (pinfunction "PA3_26") (pintype "bidirectional"))
      (node (ref "W5500-1") (pin "37") (pinfunction "37_37") (pintype "bidirectional"))
    )
    (net (code "83") (name "unconnected-(J2-PadNC)") (class "Default")
      (node (ref "J2") (pin "NC") (pinfunction "NC_NC") (pintype "bidirectional"))
    )
    (net (code "84") (name "unconnected-(U$1-PA0-Pad23)") (class "Default")
      (node (ref "U$1") (pin "23") (pinfunction "PA0_23") (pintype "bidirectional"))
    )
    (net (code "85") (name "unconnected-(U$1-PA8-Pad67)") (class "Default")
      (node (ref "U$1") (pin "67") (pinfunction "PA8_67") (pintype "bidirectional"))
    )
    (net (code "86") (name "unconnected-(U$1-PA11-Pad70)") (class "Default")
      (node (ref "U$1") (pin "70") (pinfunction "PA11_70") (pintype "bidirectional"))
    )
    (net (code "87") (name "unconnected-(U$1-PA12-Pad71)") (class "Default")
      (node (ref "U$1") (pin "71") (pinfunction "PA12_71") (pintype "bidirectional"))
    )
    (net (code "88") (name "unconnected-(U$1-PA15-Pad77)") (class "Default")
      (node (ref "U$1") (pin "77") (pinfunction "PA15_77") (pintype "bidirectional"))
    )
    (net (code "89") (name "unconnected-(U$1-PB0-Pad35)") (class "Default")
      (node (ref "U$1") (pin "35") (pinfunction "PB0_35") (pintype "bidirectional"))
    )
    (net (code "90") (name "unconnected-(U$1-PB1-Pad36)") (class "Default")
      (node (ref "U$1") (pin "36") (pinfunction "PB1_36") (pintype "bidirectional"))
    )
    (net (code "91") (name "unconnected-(U$1-PB3-Pad89)") (class "Default")
      (node (ref "U$1") (pin "89") (pinfunction "PB3_89") (pintype "bidirectional"))
    )
    (net (code "92") (name "unconnected-(U$1-PB4-Pad90)") (class "Default")
      (node (ref "U$1") (pin "90") (pinfunction "PB4_90") (pintype "bidirectional"))
    )
    (net (code "93") (name "unconnected-(U$1-PB5-Pad91)") (class "Default")
      (node (ref "U$1") (pin "91") (pinfunction "PB5_91") (pintype "bidirectional"))
    )
    (net (code "94") (name "unconnected-(U$1-PB6-Pad92)") (class "Default")
      (node (ref "U$1") (pin "92") (pinfunction "PB6_92") (pintype "bidirectional"))
    )
    (net (code "95") (name "unconnected-(U$1-PB7-Pad93)") (class "Default")
      (node (ref "U$1") (pin "93") (pinfunction "PB7_93") (pintype "bidirectional"))
    )
    (net (code "96") (name "unconnected-(U$1-PB8-Pad95)") (class "Default")
      (node (ref "U$1") (pin "95") (pinfunction "PB8_95") (pintype "bidirectional"))
    )
    (net (code "97") (name "unconnected-(U$1-PB9-Pad96)") (class "Default")
      (node (ref "U$1") (pin "96") (pinfunction "PB9_96") (pintype "bidirectional"))
    )
    (net (code "98") (name "unconnected-(U$1-PB10-Pad47)") (class "Default")
      (node (ref "U$1") (pin "47") (pinfunction "PB10_47") (pintype "bidirectional"))
    )
    (net (code "99") (name "unconnected-(U$1-PB11-Pad48)") (class "Default")
      (node (ref "U$1") (pin "48") (pinfunction "PB11_48") (pintype "bidirectional"))
    )
    (net (code "100") (name "unconnected-(U$1-PC0-Pad15)") (class "Default")
      (node (ref "U$1") (pin "15") (pinfunction "PC0_15") (pintype "bidirectional"))
    )
    (net (code "101") (name "unconnected-(U$1-PC1-Pad16)") (class "Default")
      (node (ref "U$1") (pin "16") (pinfunction "PC1_16") (pintype "bidirectional"))
    )
    (net (code "102") (name "unconnected-(U$1-PC2-Pad17)") (class "Default")
      (node (ref "U$1") (pin "17") (pinfunction "PC2_17") (pintype "bidirectional"))
    )
    (net (code "103") (name "unconnected-(U$1-PC3-Pad18)") (class "Default")
      (node (ref "U$1") (pin "18") (pinfunction "PC3_18") (pintype "bidirectional"))
    )
    (net (code "104") (name "unconnected-(U$1-PC4-Pad33)") (class "Default")
      (node (ref "U$1") (pin "33") (pinfunction "PC4_33") (pintype "bidirectional"))
    )
    (net (code "105") (name "unconnected-(U$1-PC5-Pad34)") (class "Default")
      (node (ref "U$1") (pin "34") (pinfunction "PC5_34") (pintype "bidirectional"))
    )
    (net (code "106") (name "unconnected-(U$1-PC6-Pad63)") (class "Default")
      (node (ref "U$1") (pin "63") (pinfunction "PC6_63") (pintype "bidirectional"))
    )
    (net (code "107") (name "unconnected-(U$1-PC7-Pad64)") (class "Default")
      (node (ref "U$1") (pin "64") (pinfunction "PC7_64") (pintype "bidirectional"))
    )
    (net (code "108") (name "unconnected-(U$1-PC8-Pad65)") (class "Default")
      (node (ref "U$1") (pin "65") (pinfunction "PC8_65") (pintype "bidirectional"))
    )
    (net (code "109") (name "unconnected-(U$1-PC9-Pad66)") (class "Default")
      (node (ref "U$1") (pin "66") (pinfunction "PC9_66") (pintype "bidirectional"))
    )
    (net (code "110") (name "unconnected-(U$1-PC10-Pad78)") (class "Default")
      (node (ref "U$1") (pin "78") (pinfunction "PC10_78") (pintype "bidirectional"))
    )
    (net (code "111") (name "unconnected-(U$1-PC11-Pad79)") (class "Default")
      (node (ref "U$1") (pin "79") (pinfunction "PC11_79") (pintype "bidirectional"))
    )
    (net (code "112") (name "unconnected-(U$1-PC12-Pad80)") (class "Default")
      (node (ref "U$1") (pin "80") (pinfunction "PC12_80") (pintype "bidirectional"))
    )
    (net (code "113") (name "unconnected-(U$1-PC13-Pad7)") (class "Default")
      (node (ref "U$1") (pin "7") (pinfunction "PC13_7") (pintype "bidirectional"))
    )
    (net (code "114") (name "unconnected-(U$1-PC14-Pad8)") (class "Default")
      (node (ref "U$1") (pin "8") (pinfunction "PC14_8") (pintype "bidirectional"))
    )
    (net (code "115") (name "unconnected-(U$1-PC15-Pad9)") (class "Default")
      (node (ref "U$1") (pin "9") (pinfunction "PC15_9") (pintype "bidirectional"))
    )
    (net (code "116") (name "unconnected-(U$1-PD0-Pad81)") (class "Default")
      (node (ref "U$1") (pin "81") (pinfunction "PD0_81") (pintype "bidirectional"))
    )
    (net (code "117") (name "unconnected-(U$1-PD1-Pad82)") (class "Default")
      (node (ref "U$1") (pin "82") (pinfunction "PD1_82") (pintype "bidirectional"))
    )
    (net (code "118") (name "unconnected-(U$1-PD2-Pad83)") (class "Default")
      (node (ref "U$1") (pin "83") (pinfunction "PD2_83") (pintype "bidirectional"))
    )
    (net (code "119") (name "unconnected-(U$1-PD3-Pad84)") (class "Default")
      (node (ref "U$1") (pin "84") (pinfunction "PD3_84") (pintype "bidirectional"))
    )
    (net (code "120") (name "unconnected-(U$1-PD4-Pad85)") (class "Default")
      (node (ref "U$1") (pin "85") (pinfunction "PD4_85") (pintype "bidirectional"))
    )
    (net (code "121") (name "unconnected-(U$1-PD5-Pad86)") (class "Default")
      (node (ref "U$1") (pin "86") (pinfunction "PD5_86") (pintype "bidirectional"))
    )
    (net (code "122") (name "unconnected-(U$1-PD6-Pad87)") (class "Default")
      (node (ref "U$1") (pin "87") (pinfunction "PD6_87") (pintype "bidirectional"))
    )
    (net (code "123") (name "unconnected-(U$1-PD7-Pad88)") (class "Default")
      (node (ref "U$1") (pin "88") (pinfunction "PD7_88") (pintype "bidirectional"))
    )
    (net (code "124") (name "unconnected-(U$1-PD8-Pad55)") (class "Default")
      (node (ref "U$1") (pin "55") (pinfunction "PD8_55") (pintype "bidirectional"))
    )
    (net (code "125") (name "unconnected-(U$1-PD9-Pad56)") (class "Default")
      (node (ref "U$1") (pin "56") (pinfunction "PD9_56") (pintype "bidirectional"))
    )
    (net (code "126") (name "unconnected-(U$1-PD10-Pad57)") (class "Default")
      (node (ref "U$1") (pin "57") (pinfunction "PD10_57") (pintype "bidirectional"))
    )
    (net (code "127") (name "unconnected-(U$1-PD11-Pad58)") (class "Default")
      (node (ref "U$1") (pin "58") (pinfunction "PD11_58") (pintype "bidirectional"))
    )
    (net (code "128") (name "unconnected-(U$1-PD12-Pad59)") (class "Default")
      (node (ref "U$1") (pin "59") (pinfunction "PD12_59") (pintype "bidirectional"))
    )
    (net (code "129") (name "unconnected-(U$1-PD13-Pad60)") (class "Default")
      (node (ref "U$1") (pin "60") (pinfunction "PD13_60") (pintype "bidirectional"))
    )
    (net (code "130") (name "unconnected-(U$1-PD14-Pad61)") (class "Default")
      (node (ref "U$1") (pin "61") (pinfunction "PD14_61") (pintype "bidirectional"))
    )
    (net (code "131") (name "unconnected-(U$1-PD15-Pad62)") (class "Default")
      (node (ref "U$1") (pin "62") (pinfunction "PD15_62") (pintype "bidirectional"))
    )
    (net (code "132") (name "unconnected-(U$1-PE0-Pad97)") (class "Default")
      (node (ref "U$1") (pin "97") (pinfunction "PE0_97") (pintype "bidirectional"))
    )
    (net (code "133") (name "unconnected-(U$1-PE1-Pad98)") (class "Default")
      (node (ref "U$1") (pin "98") (pinfunction "PE1_98") (pintype "bidirectional"))
    )
    (net (code "134") (name "unconnected-(U$1-PE2-Pad1)") (class "Default")
      (node (ref "U$1") (pin "1") (pinfunction "PE2_1") (pintype "bidirectional"))
    )
    (net (code "135") (name "unconnected-(U$1-PE3-Pad2)") (class "Default")
      (node (ref "U$1") (pin "2") (pinfunction "PE3_2") (pintype "bidirectional"))
    )
    (net (code "136") (name "unconnected-(U$1-PE4-Pad3)") (class "Default")
      (node (ref "U$1") (pin "3") (pinfunction "PE4_3") (pintype "bidirectional"))
    )
    (net (code "137") (name "unconnected-(U$1-PE5-Pad4)") (class "Default")
      (node (ref "U$1") (pin "4") (pinfunction "PE5_4") (pintype "bidirectional"))
    )
    (net (code "138") (name "unconnected-(U$1-PE6-Pad5)") (class "Default")
      (node (ref "U$1") (pin "5") (pinfunction "PE6_5") (pintype "bidirectional"))
    )
    (net (code "139") (name "unconnected-(U$1-PE7-Pad38)") (class "Default")
      (node (ref "U$1") (pin "38") (pinfunction "PE7_38") (pintype "bidirectional"))
    )
    (net (code "140") (name "unconnected-(U$1-PE8-Pad39)") (class "Default")
      (node (ref "U$1") (pin "39") (pinfunction "PE8_39") (pintype "bidirectional"))
    )
    (net (code "141") (name "unconnected-(U$1-PE9-Pad40)") (class "Default")
      (node (ref "U$1") (pin "40") (pinfunction "PE9_40") (pintype "bidirectional"))
    )
    (net (code "142") (name "unconnected-(U$1-PE10-Pad41)") (class "Default")
      (node (ref "U$1") (pin "41") (pinfunction "PE10_41") (pintype "bidirectional"))
    )
    (net (code "143") (name "unconnected-(U$1-PE11-Pad42)") (class "Default")
      (node (ref "U$1") (pin "42") (pinfunction "PE11_42") (pintype "bidirectional"))
    )
    (net (code "144") (name "unconnected-(U$1-PE12-Pad43)") (class "Default")
      (node (ref "U$1") (pin "43") (pinfunction "PE12_43") (pintype "bidirectional"))
    )
    (net (code "145") (name "unconnected-(U$1-PE13-Pad44)") (class "Default")
      (node (ref "U$1") (pin "44") (pinfunction "PE13_44") (pintype "bidirectional"))
    )
    (net (code "146") (name "unconnected-(U$1-PE14-Pad45)") (class "Default")
      (node (ref "U$1") (pin "45") (pinfunction "PE14_45") (pintype "bidirectional"))
    )
    (net (code "147") (name "unconnected-(U$1-PE15-Pad46)") (class "Default")
      (node (ref "U$1") (pin "46") (pinfunction "PE15_46") (pintype "bidirectional"))
    )
    (net (code "148") (name "unconnected-(U$1-VBAT-Pad6)") (class "Default")
      (node (ref "U$1") (pin "6") (pinfunction "VBAT_6") (pintype "bidirectional"))
    )
    (net (code "149") (name "unconnected-(U2-AUXOUT-Pad27)") (class "Default")
      (node (ref "U2") (pin "27") (pinfunction "AUXOUT_27") (pintype "tri_state"))
    )
    (net (code "150") (name "unconnected-(U2-ELEC_TEST-Pad33)") (class "Default")
      (node (ref "U2") (pin "33") (pinfunction "ELEC_TEST_33") (pintype "input"))
    )
    (net (code "151") (name "unconnected-(USB1-DM-Pad2)") (class "Default")
      (node (ref "USB1") (pin "2") (pinfunction "DM_2") (pintype "bidirectional"))
    )
    (net (code "152") (name "unconnected-(USB1-DP-Pad3)") (class "Default")
      (node (ref "USB1") (pin "3") (pinfunction "DP_3") (pintype "bidirectional"))
    )
    (net (code "153") (name "unconnected-(USB1-ID-Pad4)") (class "Default")
      (node (ref "USB1") (pin "4") (pinfunction "ID_4") (pintype "bidirectional"))
    )
    (net (code "154") (name "unconnected-(W5500-1-Pad7)") (class "Default")
      (node (ref "W5500-1") (pin "7") (pinfunction "7_7") (pintype "bidirectional"))
    )
    (net (code "155") (name "unconnected-(W5500-1-Pad12)") (class "Default")
      (node (ref "W5500-1") (pin "12") (pinfunction "12_12") (pintype "bidirectional"))
    )
    (net (code "156") (name "unconnected-(W5500-1-Pad13)") (class "Default")
      (node (ref "W5500-1") (pin "13") (pinfunction "13_13") (pintype "bidirectional"))
    )
    (net (code "157") (name "unconnected-(W5500-1-Pad18)") (class "Default")
      (node (ref "W5500-1") (pin "18") (pinfunction "18_18") (pintype "bidirectional"))
    )
    (net (code "158") (name "unconnected-(W5500-1-Pad24)") (class "Default")
      (node (ref "W5500-1") (pin "24") (pinfunction "24_24") (pintype "bidirectional"))
    )
    (net (code "159") (name "unconnected-(W5500-1-Pad26)") (class "Default")
      (node (ref "W5500-1") (pin "26") (pinfunction "26_26") (pintype "bidirectional"))
    )
    (net (code "160") (name "unconnected-(W5500-1-Pad46)") (class "Default")
      (node (ref "W5500-1") (pin "46") (pinfunction "46_46") (pintype "bidirectional"))
    )
    (net (code "161") (name "unconnected-(W5500-1-Pad47)") (class "Default")
      (node (ref "W5500-1") (pin "47") (pinfunction "47_47") (pintype "bidirectional"))
    )
    (net (code "162") (name "unconnected-(Y1-1-Pad4)") (class "Default")
      (node (ref "Y1") (pin "4") (pinfunction "1_4") (pintype "bidirectional"))
    )
    (net (code "163") (name "unconnected-(Y1-3-Pad2)") (class "Default")
      (node (ref "Y1") (pin "2") (pinfunction "3_2") (pintype "bidirectional"))
    )
    (net (code "164") (name "unconnected-(Y2-1-Pad4)") (class "Default")
      (node (ref "Y2") (pin "4") (pinfunction "1_4") (pintype "bidirectional"))
    )
    (net (code "165") (name "unconnected-(Y2-3-Pad2)") (class "Default")
      (node (ref "Y2") (pin "2") (pinfunction "3_2") (pintype "bidirectional"))
    )
  )
)
